# guitarduino-schematic.net
KiCad netlist of a schematic drawn in EAGLE
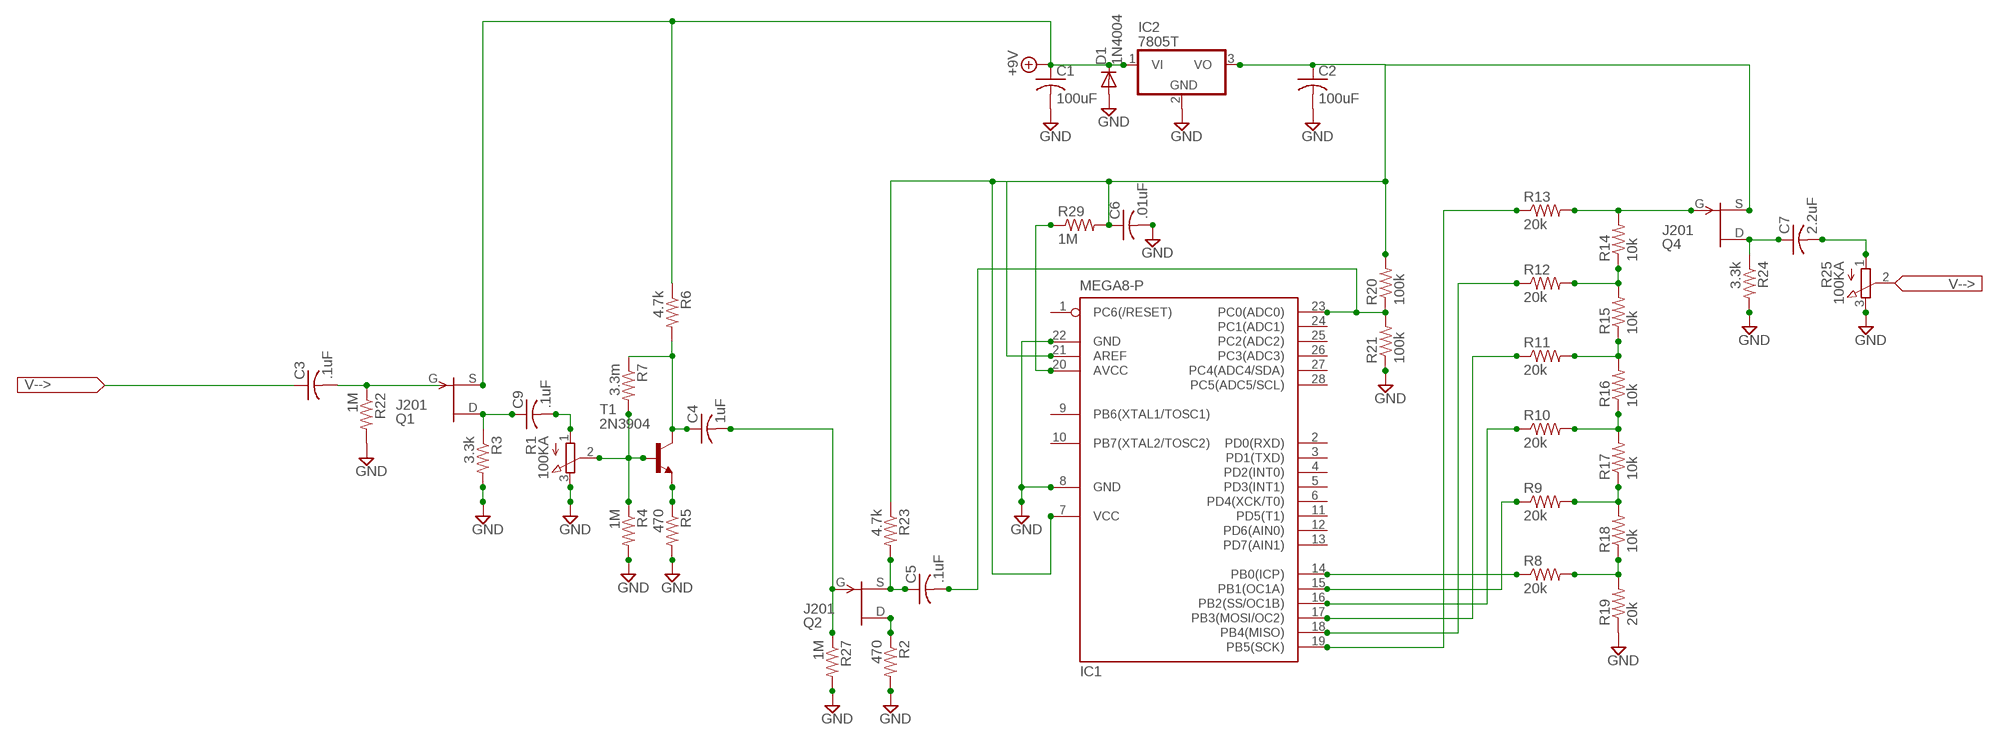
[diagram p0: schematic, sheet 1]

(export (version "E")
  (design (tool "Eeschema 10.0.6"))
  (components
    (comp (ref "C1")
      (value "100uF")
      (footprint "eagle-import:C025-025X050")
      (libsource (lib "eagle-import") (part "C-US025-025X050"))
    )
    (comp (ref "C2")
      (value "100uF")
      (footprint "eagle-import:C025-025X050")
      (libsource (lib "eagle-import") (part "C-US025-025X050"))
    )
    (comp (ref "C3")
      (value ".1uF")
      (footprint "eagle-import:C025-025X050")
      (libsource (lib "eagle-import") (part "C-US025-025X050"))
    )
    (comp (ref "C4")
      (value "1uF")
      (footprint "eagle-import:C025-025X050")
      (libsource (lib "eagle-import") (part "C-US025-025X050"))
    )
    (comp (ref "C5")
      (value ".1uF")
      (footprint "eagle-import:C025-025X050")
      (libsource (lib "eagle-import") (part "C-US025-025X050"))
    )
    (comp (ref "C6")
      (value ".01uF")
      (footprint "eagle-import:C025-025X050")
      (libsource (lib "eagle-import") (part "C-US025-025X050"))
    )
    (comp (ref "C7")
      (value "2.2uF")
      (footprint "eagle-import:C025-025X050")
      (libsource (lib "eagle-import") (part "C-US025-025X050"))
    )
    (comp (ref "C9")
      (value ".1uF")
      (footprint "eagle-import:C025-025X050")
      (libsource (lib "eagle-import") (part "C-US025-025X050"))
    )
    (comp (ref "D1")
      (value "1N4004")
      (footprint "eagle-import:DO41-10")
      (libsource (lib "eagle-import") (part "1N4004"))
    )
    (comp (ref "IC1")
      (value "MEGA8-P")
      (footprint "eagle-import:DIL28-3")
      (libsource (lib "eagle-import") (part "MEGA8-P"))
    )
    (comp (ref "IC2")
      (value "7805T")
      (footprint "eagle-import:TO220H")
      (libsource (lib "eagle-import") (part "78T05"))
    )
    (comp (ref "Q1")
      (value "J201")
      (footprint "eagle-import:TO92")
      (libsource (lib "eagle-import") (part "?20J1"))
    )
    (comp (ref "Q2")
      (value "J201")
      (footprint "eagle-import:TO92")
      (libsource (lib "eagle-import") (part "?20J1"))
    )
    (comp (ref "Q4")
      (value "J201")
      (footprint "eagle-import:TO92")
      (libsource (lib "eagle-import") (part "?20J1"))
    )
    (comp (ref "R1")
      (value "100KA")
      (footprint "eagle-import:3RP_1610N")
      (libsource (lib "eagle-import") (part "3RP/1610N"))
    )
    (comp (ref "R2")
      (value "470")
      (footprint "eagle-import:0207_7")
      (libsource (lib "eagle-import") (part "R-US_0207/7"))
    )
    (comp (ref "R3")
      (value "3.3k")
      (footprint "eagle-import:0207_7")
      (libsource (lib "eagle-import") (part "R-US_0207/7"))
    )
    (comp (ref "R4")
      (value "1M")
      (footprint "eagle-import:0207_7")
      (libsource (lib "eagle-import") (part "R-US_0207/7"))
    )
    (comp (ref "R5")
      (value "470")
      (footprint "eagle-import:0207_7")
      (libsource (lib "eagle-import") (part "R-US_0207/7"))
    )
    (comp (ref "R6")
      (value "4.7k")
      (footprint "eagle-import:0207_7")
      (libsource (lib "eagle-import") (part "R-US_0207/7"))
    )
    (comp (ref "R7")
      (value "3.3m")
      (footprint "eagle-import:0207_7")
      (libsource (lib "eagle-import") (part "R-US_0207/7"))
    )
    (comp (ref "R8")
      (value "20k")
      (footprint "eagle-import:0207_7")
      (libsource (lib "eagle-import") (part "R-US_0207/7"))
    )
    (comp (ref "R9")
      (value "20k")
      (footprint "eagle-import:0207_7")
      (libsource (lib "eagle-import") (part "R-US_0207/7"))
    )
    (comp (ref "R10")
      (value "20k")
      (footprint "eagle-import:0207_7")
      (libsource (lib "eagle-import") (part "R-US_0207/7"))
    )
    (comp (ref "R11")
      (value "20k")
      (footprint "eagle-import:0207_7")
      (libsource (lib "eagle-import") (part "R-US_0207/7"))
    )
    (comp (ref "R12")
      (value "20k")
      (footprint "eagle-import:0207_7")
      (libsource (lib "eagle-import") (part "R-US_0207/7"))
    )
    (comp (ref "R13")
      (value "20k")
      (footprint "eagle-import:0207_7")
      (libsource (lib "eagle-import") (part "R-US_0207/7"))
    )
    (comp (ref "R14")
      (value "10k")
      (footprint "eagle-import:0207_7")
      (libsource (lib "eagle-import") (part "R-US_0207/7"))
    )
    (comp (ref "R15")
      (value "10k")
      (footprint "eagle-import:0207_7")
      (libsource (lib "eagle-import") (part "R-US_0207/7"))
    )
    (comp (ref "R16")
      (value "10k")
      (footprint "eagle-import:0207_7")
      (libsource (lib "eagle-import") (part "R-US_0207/7"))
    )
    (comp (ref "R17")
      (value "10k")
      (footprint "eagle-import:0207_7")
      (libsource (lib "eagle-import") (part "R-US_0207/7"))
    )
    (comp (ref "R18")
      (value "10k")
      (footprint "eagle-import:0207_7")
      (libsource (lib "eagle-import") (part "R-US_0207/7"))
    )
    (comp (ref "R19")
      (value "20k")
      (footprint "eagle-import:0207_7")
      (libsource (lib "eagle-import") (part "R-US_0207/7"))
    )
    (comp (ref "R20")
      (value "100k")
      (footprint "eagle-import:0204_7")
      (libsource (lib "eagle-import") (part "R-US_0204/7"))
    )
    (comp (ref "R21")
      (value "100k")
      (footprint "eagle-import:0204_7")
      (libsource (lib "eagle-import") (part "R-US_0204/7"))
    )
    (comp (ref "R22")
      (value "1M")
      (footprint "eagle-import:0207_7")
      (libsource (lib "eagle-import") (part "R-US_0207/7"))
    )
    (comp (ref "R23")
      (value "4.7k")
      (footprint "eagle-import:0207_7")
      (libsource (lib "eagle-import") (part "R-US_0207/7"))
    )
    (comp (ref "R24")
      (value "3.3k")
      (footprint "eagle-import:0207_7")
      (libsource (lib "eagle-import") (part "R-US_0207/7"))
    )
    (comp (ref "R25")
      (value "100KA")
      (footprint "eagle-import:3RP_1610N")
      (libsource (lib "eagle-import") (part "3RP/1610N"))
    )
    (comp (ref "R27")
      (value "1M")
      (footprint "eagle-import:0207_7")
      (libsource (lib "eagle-import") (part "R-US_0207/7"))
    )
    (comp (ref "R29")
      (value "1M")
      (footprint "eagle-import:0207_7")
      (libsource (lib "eagle-import") (part "R-US_0207/7"))
    )
    (comp (ref "T1")
      (value "2N3904")
      (footprint "eagle-import:TO92")
      (libsource (lib "eagle-import") (part "2N3904"))
    )
  )
  (nets
    (net (code "1") (name "+9V") (class "Default")
      (node (ref "C1") (pin "1") (pinfunction "1_1") (pintype "passive"))
      (node (ref "D1") (pin "C") (pinfunction "C_C") (pintype "passive"))
      (node (ref "IC2") (pin "1") (pinfunction "VI_1") (pintype "input"))
      (node (ref "Q1") (pin "2") (pinfunction "S_2") (pintype "passive"))
      (node (ref "R6") (pin "1") (pinfunction "1_1") (pintype "passive"))
    )
    (net (code "2") (name "GND") (class "Default")
      (node (ref "C1") (pin "2") (pinfunction "2_2") (pintype "passive"))
      (node (ref "C2") (pin "2") (pinfunction "2_2") (pintype "passive"))
      (node (ref "C6") (pin "2") (pinfunction "2_2") (pintype "passive"))
      (node (ref "D1") (pin "A") (pinfunction "A_A") (pintype "passive"))
      (node (ref "IC1") (pin "22") (pinfunction "GND_22") (pintype "power_in"))
      (node (ref "IC1") (pin "8") (pinfunction "GND_8") (pintype "power_in"))
      (node (ref "IC2") (pin "2") (pinfunction "GND_2") (pintype "passive"))
      (node (ref "R1") (pin "3") (pinfunction "E_3") (pintype "passive"))
      (node (ref "R19") (pin "1") (pinfunction "1_1") (pintype "passive"))
      (node (ref "R2") (pin "2") (pinfunction "2_2") (pintype "passive"))
      (node (ref "R21") (pin "1") (pinfunction "1_1") (pintype "passive"))
      (node (ref "R22") (pin "2") (pinfunction "2_2") (pintype "passive"))
      (node (ref "R24") (pin "2") (pinfunction "2_2") (pintype "passive"))
      (node (ref "R25") (pin "3") (pinfunction "E_3") (pintype "passive"))
      (node (ref "R27") (pin "2") (pinfunction "2_2") (pintype "passive"))
      (node (ref "R3") (pin "2") (pinfunction "2_2") (pintype "passive"))
      (node (ref "R4") (pin "2") (pinfunction "2_2") (pintype "passive"))
      (node (ref "R5") (pin "2") (pinfunction "2_2") (pintype "passive"))
    )
    (net (code "3") (name "Net-(IC1-AREF)") (class "Default")
      (node (ref "C2") (pin "1") (pinfunction "1_1") (pintype "passive"))
      (node (ref "C6") (pin "1") (pinfunction "1_1") (pintype "passive"))
      (node (ref "IC1") (pin "21") (pinfunction "AREF_21") (pintype "passive"))
      (node (ref "IC1") (pin "7") (pinfunction "VCC_7") (pintype "power_in"))
      (node (ref "IC2") (pin "3") (pinfunction "VO_3") (pintype "passive"))
      (node (ref "Q4") (pin "2") (pinfunction "S_2") (pintype "passive"))
      (node (ref "R20") (pin "2") (pinfunction "2_2") (pintype "passive"))
      (node (ref "R23") (pin "1") (pinfunction "1_1") (pintype "passive"))
      (node (ref "R29") (pin "2") (pinfunction "2_2") (pintype "passive"))
    )
    (net (code "4") (name "Net-(IC1-AVCC)") (class "Default")
      (node (ref "IC1") (pin "20") (pinfunction "AVCC_20") (pintype "power_in"))
      (node (ref "R29") (pin "1") (pinfunction "1_1") (pintype "passive"))
    )
    (net (code "5") (name "Net-(IC1-PB0(ICP))") (class "Default")
      (node (ref "IC1") (pin "14") (pinfunction "PB0(ICP)_14") (pintype "bidirectional"))
      (node (ref "R8") (pin "1") (pinfunction "1_1") (pintype "passive"))
    )
    (net (code "6") (name "Net-(IC1-PB1(OC1A))") (class "Default")
      (node (ref "IC1") (pin "15") (pinfunction "PB1(OC1A)_15") (pintype "bidirectional"))
      (node (ref "R9") (pin "1") (pinfunction "1_1") (pintype "passive"))
    )
    (net (code "7") (name "Net-(IC1-PB2(SS{slash}OC1B))") (class "Default")
      (node (ref "IC1") (pin "16") (pinfunction "PB2(SS/OC1B)_16") (pintype "bidirectional"))
      (node (ref "R10") (pin "1") (pinfunction "1_1") (pintype "passive"))
    )
    (net (code "8") (name "Net-(IC1-PB3(MOSI{slash}OC2))") (class "Default")
      (node (ref "IC1") (pin "17") (pinfunction "PB3(MOSI/OC2)_17") (pintype "bidirectional"))
      (node (ref "R11") (pin "1") (pinfunction "1_1") (pintype "passive"))
    )
    (net (code "9") (name "Net-(IC1-PB4(MISO))") (class "Default")
      (node (ref "IC1") (pin "18") (pinfunction "PB4(MISO)_18") (pintype "bidirectional"))
      (node (ref "R12") (pin "1") (pinfunction "1_1") (pintype "passive"))
    )
    (net (code "10") (name "Net-(IC1-PB5(SCK))") (class "Default")
      (node (ref "IC1") (pin "19") (pinfunction "PB5(SCK)_19") (pintype "bidirectional"))
      (node (ref "R13") (pin "1") (pinfunction "1_1") (pintype "passive"))
    )
    (net (code "11") (name "Net-(IC1-PC0(ADC0))") (class "Default")
      (node (ref "C5") (pin "2") (pinfunction "2_2") (pintype "passive"))
      (node (ref "IC1") (pin "23") (pinfunction "PC0(ADC0)_23") (pintype "bidirectional"))
      (node (ref "R20") (pin "1") (pinfunction "1_1") (pintype "passive"))
      (node (ref "R21") (pin "2") (pinfunction "2_2") (pintype "passive"))
    )
    (net (code "12") (name "Net-(Q1-D)") (class "Default")
      (node (ref "C9") (pin "1") (pinfunction "1_1") (pintype "passive"))
      (node (ref "Q1") (pin "3") (pinfunction "D_3") (pintype "passive"))
      (node (ref "R3") (pin "1") (pinfunction "1_1") (pintype "passive"))
    )
    (net (code "13") (name "Net-(Q1-G)") (class "Default")
      (node (ref "C3") (pin "2") (pinfunction "2_2") (pintype "passive"))
      (node (ref "Q1") (pin "1") (pinfunction "G_1") (pintype "passive"))
      (node (ref "R22") (pin "1") (pinfunction "1_1") (pintype "passive"))
    )
    (net (code "14") (name "Net-(Q2-D)") (class "Default")
      (node (ref "Q2") (pin "3") (pinfunction "D_3") (pintype "passive"))
      (node (ref "R2") (pin "1") (pinfunction "1_1") (pintype "passive"))
    )
    (net (code "15") (name "Net-(Q2-G)") (class "Default")
      (node (ref "C4") (pin "2") (pinfunction "2_2") (pintype "passive"))
      (node (ref "Q2") (pin "1") (pinfunction "G_1") (pintype "passive"))
      (node (ref "R27") (pin "1") (pinfunction "1_1") (pintype "passive"))
    )
    (net (code "16") (name "Net-(Q2-S)") (class "Default")
      (node (ref "C5") (pin "1") (pinfunction "1_1") (pintype "passive"))
      (node (ref "Q2") (pin "2") (pinfunction "S_2") (pintype "passive"))
      (node (ref "R23") (pin "2") (pinfunction "2_2") (pintype "passive"))
    )
    (net (code "17") (name "Net-(Q4-D)") (class "Default")
      (node (ref "C7") (pin "1") (pinfunction "1_1") (pintype "passive"))
      (node (ref "Q4") (pin "3") (pinfunction "D_3") (pintype "passive"))
      (node (ref "R24") (pin "1") (pinfunction "1_1") (pintype "passive"))
    )
    (net (code "18") (name "Net-(Q4-G)") (class "Default")
      (node (ref "Q4") (pin "1") (pinfunction "G_1") (pintype "passive"))
      (node (ref "R13") (pin "2") (pinfunction "2_2") (pintype "passive"))
      (node (ref "R14") (pin "2") (pinfunction "2_2") (pintype "passive"))
    )
    (net (code "19") (name "Net-(R1-A)") (class "Default")
      (node (ref "C9") (pin "2") (pinfunction "2_2") (pintype "passive"))
      (node (ref "R1") (pin "1") (pinfunction "A_1") (pintype "passive"))
    )
    (net (code "20") (name "Net-(R1-S)") (class "Default")
      (node (ref "R1") (pin "2") (pinfunction "S_2") (pintype "passive"))
      (node (ref "R4") (pin "1") (pinfunction "1_1") (pintype "passive"))
      (node (ref "R7") (pin "2") (pinfunction "2_2") (pintype "passive"))
      (node (ref "T1") (pin "2") (pinfunction "B_2") (pintype "passive"))
    )
    (net (code "21") (name "Net-(R10-Pad2)") (class "Default")
      (node (ref "R10") (pin "2") (pinfunction "2_2") (pintype "passive"))
      (node (ref "R16") (pin "1") (pinfunction "1_1") (pintype "passive"))
      (node (ref "R17") (pin "2") (pinfunction "2_2") (pintype "passive"))
    )
    (net (code "22") (name "Net-(R11-Pad2)") (class "Default")
      (node (ref "R11") (pin "2") (pinfunction "2_2") (pintype "passive"))
      (node (ref "R15") (pin "1") (pinfunction "1_1") (pintype "passive"))
      (node (ref "R16") (pin "2") (pinfunction "2_2") (pintype "passive"))
    )
    (net (code "23") (name "Net-(R12-Pad2)") (class "Default")
      (node (ref "R12") (pin "2") (pinfunction "2_2") (pintype "passive"))
      (node (ref "R14") (pin "1") (pinfunction "1_1") (pintype "passive"))
      (node (ref "R15") (pin "2") (pinfunction "2_2") (pintype "passive"))
    )
    (net (code "24") (name "Net-(R17-Pad1)") (class "Default")
      (node (ref "R17") (pin "1") (pinfunction "1_1") (pintype "passive"))
      (node (ref "R18") (pin "2") (pinfunction "2_2") (pintype "passive"))
      (node (ref "R9") (pin "2") (pinfunction "2_2") (pintype "passive"))
    )
    (net (code "25") (name "Net-(R18-Pad1)") (class "Default")
      (node (ref "R18") (pin "1") (pinfunction "1_1") (pintype "passive"))
      (node (ref "R19") (pin "2") (pinfunction "2_2") (pintype "passive"))
      (node (ref "R8") (pin "2") (pinfunction "2_2") (pintype "passive"))
    )
    (net (code "26") (name "Net-(R25-A)") (class "Default")
      (node (ref "C7") (pin "2") (pinfunction "2_2") (pintype "passive"))
      (node (ref "R25") (pin "1") (pinfunction "A_1") (pintype "passive"))
    )
    (net (code "27") (name "Net-(T1-C)") (class "Default")
      (node (ref "C4") (pin "1") (pinfunction "1_1") (pintype "passive"))
      (node (ref "R6") (pin "2") (pinfunction "2_2") (pintype "passive"))
      (node (ref "R7") (pin "1") (pinfunction "1_1") (pintype "passive"))
      (node (ref "T1") (pin "1") (pinfunction "C_1") (pintype "passive"))
    )
    (net (code "28") (name "Net-(T1-E)") (class "Default")
      (node (ref "R5") (pin "1") (pinfunction "1_1") (pintype "passive"))
      (node (ref "T1") (pin "3") (pinfunction "E_3") (pintype "passive"))
    )
    (net (code "29") (name "unconnected-(C3-Pad1)") (class "Default")
      (node (ref "C3") (pin "1") (pinfunction "1_1") (pintype "passive"))
    )
    (net (code "30") (name "unconnected-(IC1-PB6(XTAL1{slash}TOSC1)-Pad9)") (class "Default")
      (node (ref "IC1") (pin "9") (pinfunction "PB6(XTAL1/TOSC1)_9") (pintype "bidirectional"))
    )
    (net (code "31") (name "unconnected-(IC1-PB7(XTAL2{slash}TOSC2)-Pad10)") (class "Default")
      (node (ref "IC1") (pin "10") (pinfunction "PB7(XTAL2/TOSC2)_10") (pintype "bidirectional"))
    )
    (net (code "32") (name "unconnected-(IC1-PC1(ADC1)-Pad24)") (class "Default")
      (node (ref "IC1") (pin "24") (pinfunction "PC1(ADC1)_24") (pintype "bidirectional"))
    )
    (net (code "33") (name "unconnected-(IC1-PC2(ADC2)-Pad25)") (class "Default")
      (node (ref "IC1") (pin "25") (pinfunction "PC2(ADC2)_25") (pintype "bidirectional"))
    )
    (net (code "34") (name "unconnected-(IC1-PC3(ADC3)-Pad26)") (class "Default")
      (node (ref "IC1") (pin "26") (pinfunction "PC3(ADC3)_26") (pintype "bidirectional"))
    )
    (net (code "35") (name "unconnected-(IC1-PC4(ADC4{slash}SDA)-Pad27)") (class "Default")
      (node (ref "IC1") (pin "27") (pinfunction "PC4(ADC4/SDA)_27") (pintype "bidirectional"))
    )
    (net (code "36") (name "unconnected-(IC1-PC5(ADC5{slash}SCL)-Pad28)") (class "Default")
      (node (ref "IC1") (pin "28") (pinfunction "PC5(ADC5/SCL)_28") (pintype "bidirectional"))
    )
    (net (code "37") (name "unconnected-(IC1-PC6({slash}RESET)-Pad1)") (class "Default")
      (node (ref "IC1") (pin "1") (pinfunction "PC6(/RESET)_1") (pintype "bidirectional"))
    )
    (net (code "38") (name "unconnected-(IC1-PD0(RXD)-Pad2)") (class "Default")
      (node (ref "IC1") (pin "2") (pinfunction "PD0(RXD)_2") (pintype "bidirectional"))
    )
    (net (code "39") (name "unconnected-(IC1-PD1(TXD)-Pad3)") (class "Default")
      (node (ref "IC1") (pin "3") (pinfunction "PD1(TXD)_3") (pintype "bidirectional"))
    )
    (net (code "40") (name "unconnected-(IC1-PD2(INT0)-Pad4)") (class "Default")
      (node (ref "IC1") (pin "4") (pinfunction "PD2(INT0)_4") (pintype "bidirectional"))
    )
    (net (code "41") (name "unconnected-(IC1-PD3(INT1)-Pad5)") (class "Default")
      (node (ref "IC1") (pin "5") (pinfunction "PD3(INT1)_5") (pintype "bidirectional"))
    )
    (net (code "42") (name "unconnected-(IC1-PD4(XCK{slash}T0)-Pad6)") (class "Default")
      (node (ref "IC1") (pin "6") (pinfunction "PD4(XCK/T0)_6") (pintype "bidirectional"))
    )
    (net (code "43") (name "unconnected-(IC1-PD5(T1)-Pad11)") (class "Default")
      (node (ref "IC1") (pin "11") (pinfunction "PD5(T1)_11") (pintype "bidirectional"))
    )
    (net (code "44") (name "unconnected-(IC1-PD6(AIN0)-Pad12)") (class "Default")
      (node (ref "IC1") (pin "12") (pinfunction "PD6(AIN0)_12") (pintype "bidirectional"))
    )
    (net (code "45") (name "unconnected-(IC1-PD7(AIN1)-Pad13)") (class "Default")
      (node (ref "IC1") (pin "13") (pinfunction "PD7(AIN1)_13") (pintype "bidirectional"))
    )
    (net (code "46") (name "unconnected-(R25-S-Pad2)") (class "Default")
      (node (ref "R25") (pin "2") (pinfunction "S_2") (pintype "passive"))
    )
  )
)
